# H723_AD9280_AD9708.net
KiCad netlist of a schematic drawn in EasyEDA Pro
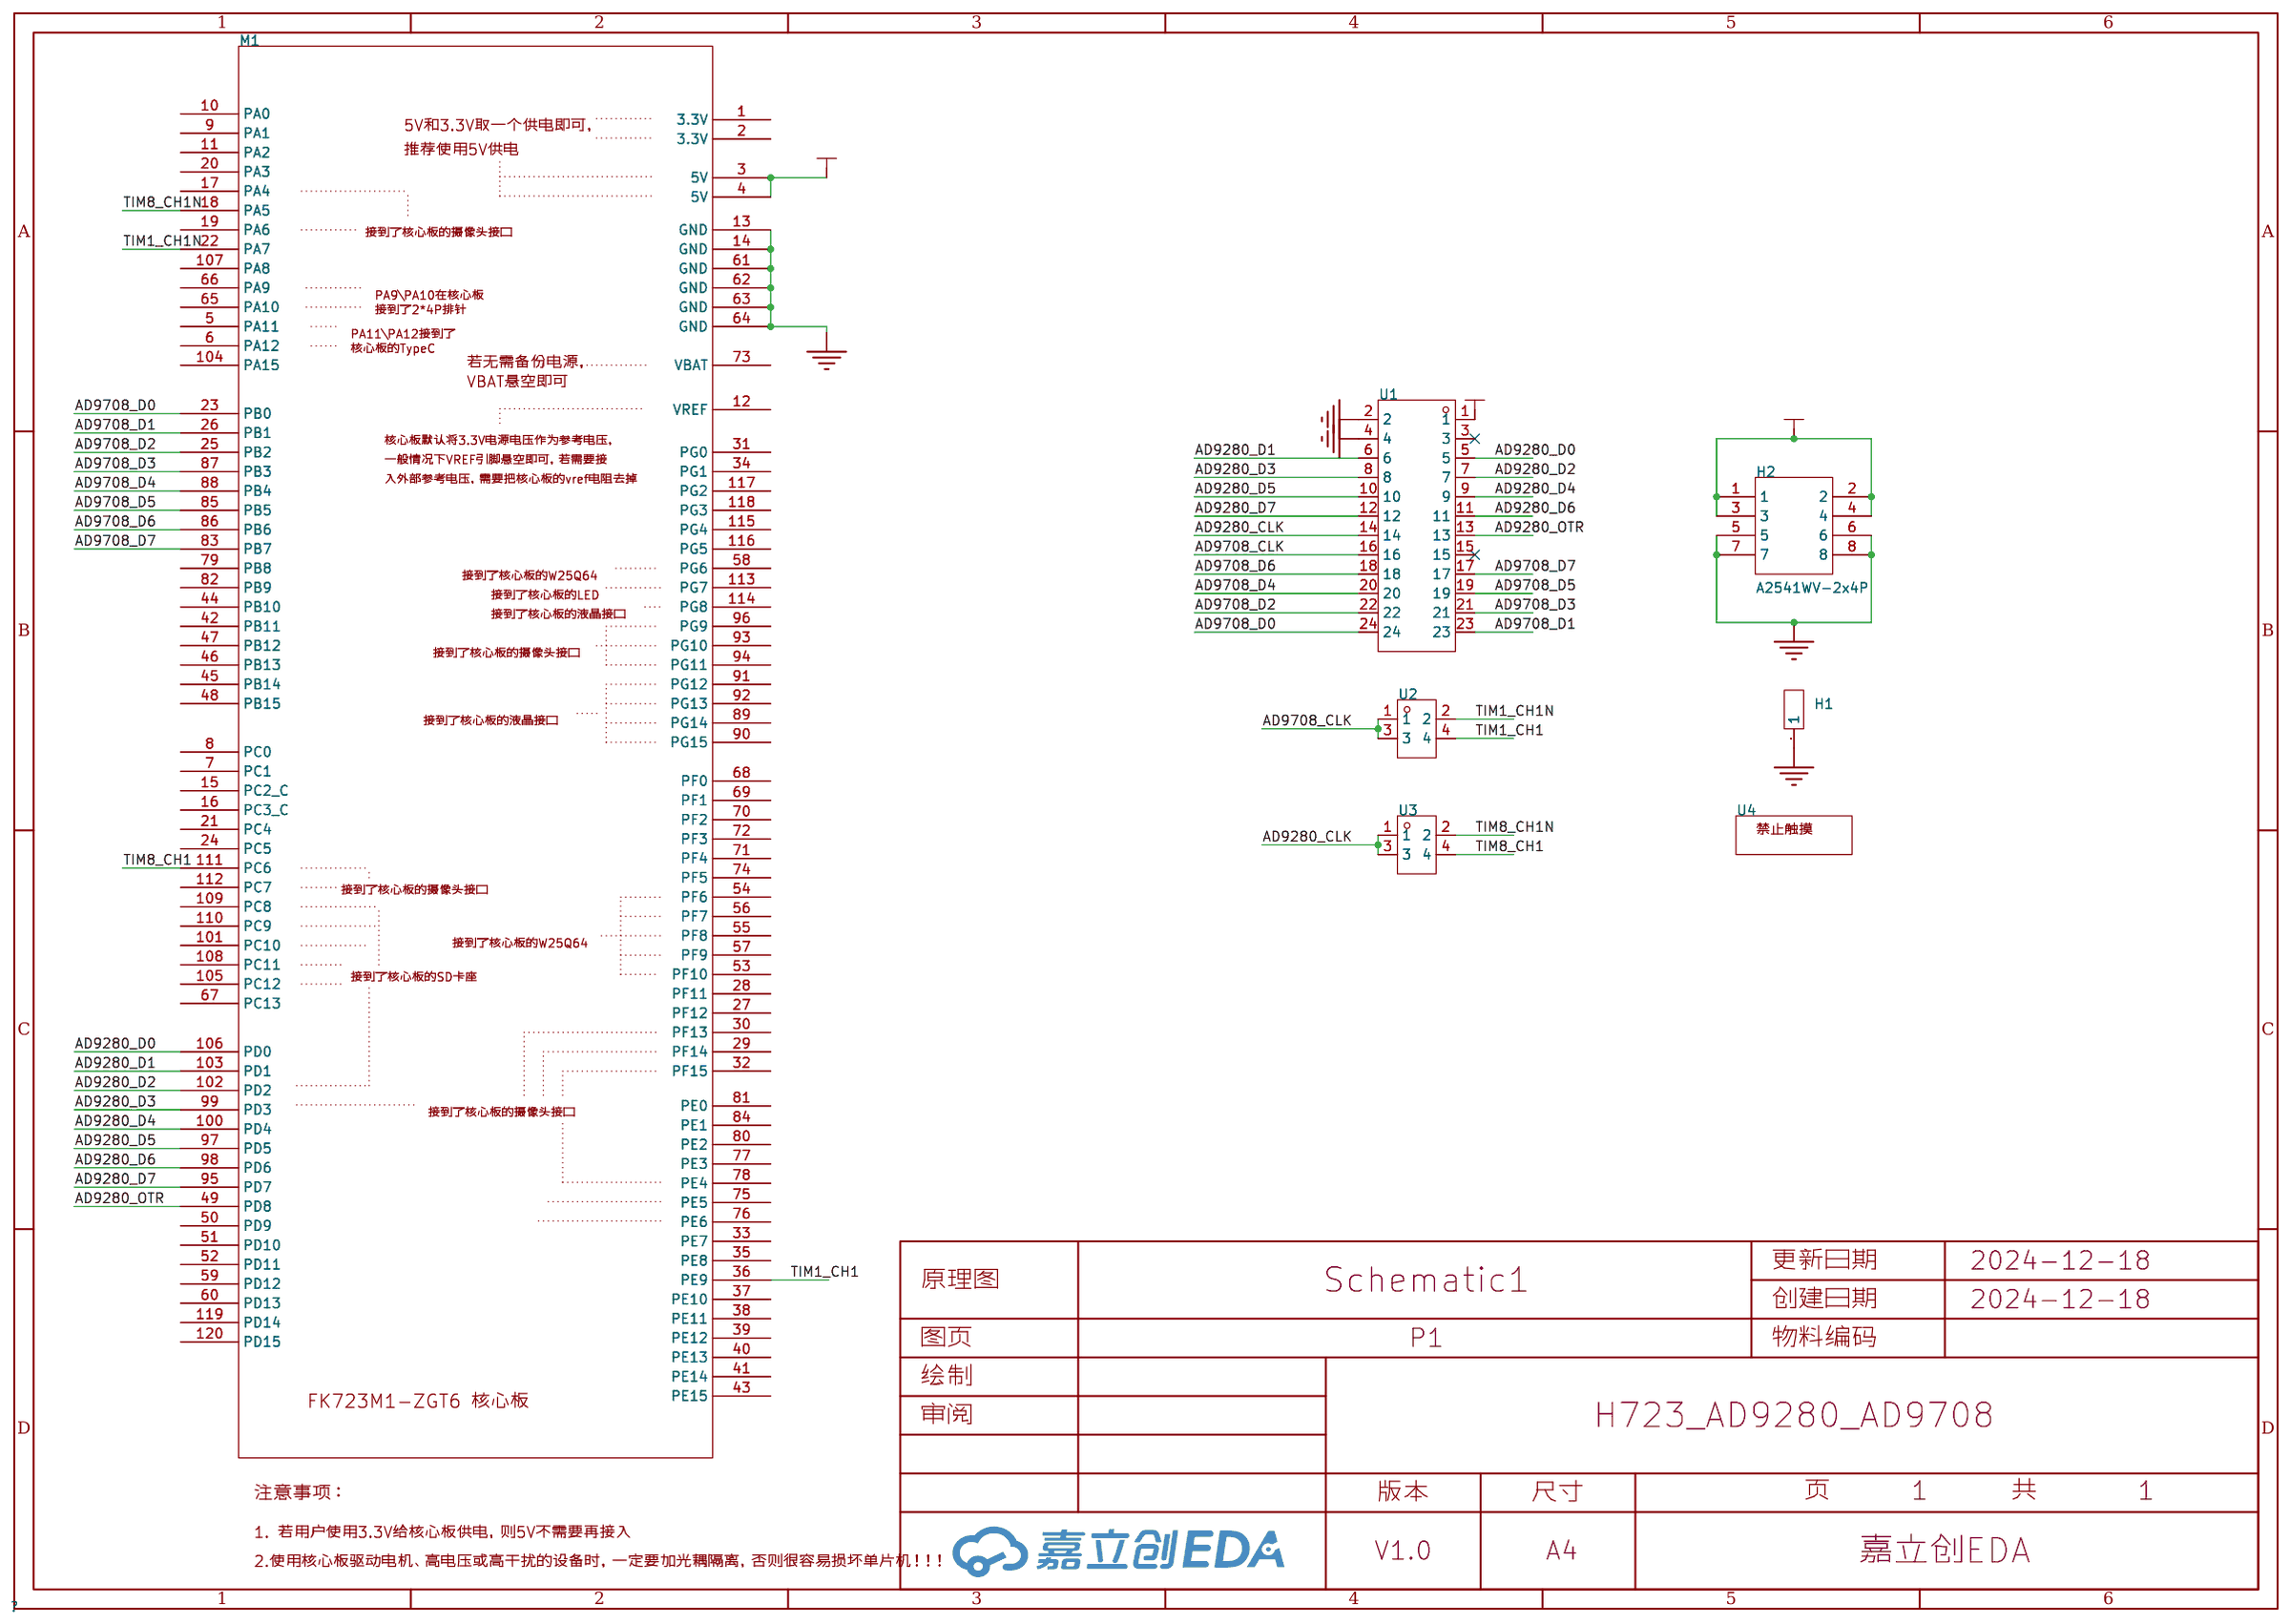
[diagram p0: schematic sheet]

(export (version "E")
  (design (tool "Eeschema 10.0.6"))
  (components
    (comp (ref "H1")
      (value "~")
      (footprint "easyedapro:HDR-TH_1P-V-M_XKB_X4611WV-01I-C28D40")
      (libsource (lib "easyedapro") (part "HDR_1x1"))
    )
    (comp (ref "H2")
      (value "A2541WV-2x4P")
      (footprint "easyedapro:HDR-TH_8P-P2.54-V-R2-C4-S2.54_A2541WV-2X4P")
      (fields (field (name "Manufacturer") "CJT(长江连接器)"))
      (libsource (lib "easyedapro") (part "A2541WV-2X4P"))
    )
    (comp (ref "M1")
      (value "~")
      (footprint "easyedapro:FK723M1-ZGT6")
      (libsource (lib "easyedapro") (part "FK723M1-ZGT6"))
    )
    (comp (ref "U1")
      (value "2541WV-2x12P")
      (footprint "easyedapro:HDR-TH_24P-P2.54-V-M-R2-C12-S2.54")
      (description "插针结构:2x12P;间距:2.54mm;安装类型:直插;排数:双排;总PIN位数:24P;配合针长度:6mm;塑高:2.54mm;端接针长度:3mm;")
      (fields (field (name "Manufacturer") "HanElectricity(瀚源)"))
      (libsource (lib "easyedapro") (part "2541WV-2X12P"))
    )
    (comp (ref "U2")
      (value "2541WV-2x02P")
      (footprint "easyedapro:HDR-TH_4P-P2.54-V-M-R2-C2-S2.54")
      (description "插针结构:2x2P;间距:2.54mm;安装类型:直插;排数:双排;总PIN位数:4P;配合针长度:6mm;塑高:2.54mm;端接针长度:3mm;")
      (fields (field (name "Manufacturer") "HanElectricity(瀚源)"))
      (libsource (lib "easyedapro") (part "2541WV-2X02P"))
    )
    (comp (ref "U3")
      (value "2541WV-2x02P")
      (footprint "easyedapro:HDR-TH_4P-P2.54-V-M-R2-C2-S2.54")
      (description "插针结构:2x2P;间距:2.54mm;安装类型:直插;排数:双排;总PIN位数:4P;配合针长度:6mm;塑高:2.54mm;端接针长度:3mm;")
      (fields (field (name "Manufacturer") "HanElectricity(瀚源)"))
      (libsource (lib "easyedapro") (part "2541WV-2X02P"))
    )
    (comp (ref "U4")
      (value "~")
      (footprint "easyedapro:禁止触摸LOGO")
      (libsource (lib "easyedapro") (part "禁止触摸LOGO"))
    )
  )
  (nets
    (net (code "1") (name "/AD9280_CLK") (class "Default")
      (node (ref "U1") (pin "14") (pinfunction "14_14") (pintype "unspecified"))
      (node (ref "U3") (pin "1") (pinfunction "1_1") (pintype "unspecified"))
      (node (ref "U3") (pin "3") (pinfunction "3_3") (pintype "unspecified"))
    )
    (net (code "2") (name "/AD9280_D0") (class "Default")
      (node (ref "M1") (pin "106") (pinfunction "PD0_106") (pintype "unspecified"))
      (node (ref "U1") (pin "5") (pinfunction "5_5") (pintype "unspecified"))
    )
    (net (code "3") (name "/AD9280_D1") (class "Default")
      (node (ref "M1") (pin "103") (pinfunction "PD1_103") (pintype "unspecified"))
      (node (ref "U1") (pin "6") (pinfunction "6_6") (pintype "unspecified"))
    )
    (net (code "4") (name "/AD9280_D2") (class "Default")
      (node (ref "M1") (pin "102") (pinfunction "PD2_102") (pintype "unspecified"))
      (node (ref "U1") (pin "7") (pinfunction "7_7") (pintype "unspecified"))
    )
    (net (code "5") (name "/AD9280_D3") (class "Default")
      (node (ref "M1") (pin "99") (pinfunction "PD3_99") (pintype "unspecified"))
      (node (ref "U1") (pin "8") (pinfunction "8_8") (pintype "unspecified"))
    )
    (net (code "6") (name "/AD9280_D4") (class "Default")
      (node (ref "M1") (pin "100") (pinfunction "PD4_100") (pintype "unspecified"))
      (node (ref "U1") (pin "9") (pinfunction "9_9") (pintype "unspecified"))
    )
    (net (code "7") (name "/AD9280_D5") (class "Default")
      (node (ref "M1") (pin "97") (pinfunction "PD5_97") (pintype "unspecified"))
      (node (ref "U1") (pin "10") (pinfunction "10_10") (pintype "unspecified"))
    )
    (net (code "8") (name "/AD9280_D6") (class "Default")
      (node (ref "M1") (pin "98") (pinfunction "PD6_98") (pintype "unspecified"))
      (node (ref "U1") (pin "11") (pinfunction "11_11") (pintype "unspecified"))
    )
    (net (code "9") (name "/AD9280_D7") (class "Default")
      (node (ref "M1") (pin "95") (pinfunction "PD7_95") (pintype "unspecified"))
      (node (ref "U1") (pin "12") (pinfunction "12_12") (pintype "unspecified"))
    )
    (net (code "10") (name "/AD9280_OTR") (class "Default")
      (node (ref "M1") (pin "49") (pinfunction "PD8_49") (pintype "unspecified"))
      (node (ref "U1") (pin "13") (pinfunction "13_13") (pintype "unspecified"))
    )
    (net (code "11") (name "/AD9708_CLK") (class "Default")
      (node (ref "U1") (pin "16") (pinfunction "16_16") (pintype "unspecified"))
      (node (ref "U2") (pin "1") (pinfunction "1_1") (pintype "unspecified"))
      (node (ref "U2") (pin "3") (pinfunction "3_3") (pintype "unspecified"))
    )
    (net (code "12") (name "/AD9708_D0") (class "Default")
      (node (ref "M1") (pin "23") (pinfunction "PB0_23") (pintype "unspecified"))
      (node (ref "U1") (pin "24") (pinfunction "24_24") (pintype "unspecified"))
    )
    (net (code "13") (name "/AD9708_D1") (class "Default")
      (node (ref "M1") (pin "26") (pinfunction "PB1_26") (pintype "unspecified"))
      (node (ref "U1") (pin "23") (pinfunction "23_23") (pintype "unspecified"))
    )
    (net (code "14") (name "/AD9708_D2") (class "Default")
      (node (ref "M1") (pin "25") (pinfunction "PB2_25") (pintype "unspecified"))
      (node (ref "U1") (pin "22") (pinfunction "22_22") (pintype "unspecified"))
    )
    (net (code "15") (name "/AD9708_D3") (class "Default")
      (node (ref "M1") (pin "87") (pinfunction "PB3_87") (pintype "unspecified"))
      (node (ref "U1") (pin "21") (pinfunction "21_21") (pintype "unspecified"))
    )
    (net (code "16") (name "/AD9708_D4") (class "Default")
      (node (ref "M1") (pin "88") (pinfunction "PB4_88") (pintype "unspecified"))
      (node (ref "U1") (pin "20") (pinfunction "20_20") (pintype "unspecified"))
    )
    (net (code "17") (name "/AD9708_D5") (class "Default")
      (node (ref "M1") (pin "85") (pinfunction "PB5_85") (pintype "unspecified"))
      (node (ref "U1") (pin "19") (pinfunction "19_19") (pintype "unspecified"))
    )
    (net (code "18") (name "/AD9708_D6") (class "Default")
      (node (ref "M1") (pin "86") (pinfunction "PB6_86") (pintype "unspecified"))
      (node (ref "U1") (pin "18") (pinfunction "18_18") (pintype "unspecified"))
    )
    (net (code "19") (name "/AD9708_D7") (class "Default")
      (node (ref "M1") (pin "83") (pinfunction "PB7_83") (pintype "unspecified"))
      (node (ref "U1") (pin "17") (pinfunction "17_17") (pintype "unspecified"))
    )
    (net (code "20") (name "/TIM1_CH1") (class "Default")
      (node (ref "M1") (pin "36") (pinfunction "PE9_36") (pintype "unspecified"))
      (node (ref "U2") (pin "4") (pinfunction "4_4") (pintype "unspecified"))
    )
    (net (code "21") (name "/TIM1_CH1N") (class "Default")
      (node (ref "M1") (pin "22") (pinfunction "PA7_22") (pintype "unspecified"))
      (node (ref "U2") (pin "2") (pinfunction "2_2") (pintype "unspecified"))
    )
    (net (code "22") (name "/TIM8_CH1") (class "Default")
      (node (ref "M1") (pin "111") (pinfunction "PC6_111") (pintype "unspecified"))
      (node (ref "U3") (pin "4") (pinfunction "4_4") (pintype "unspecified"))
    )
    (net (code "23") (name "/TIM8_CH1N") (class "Default")
      (node (ref "M1") (pin "18") (pinfunction "PA5_18") (pintype "unspecified"))
      (node (ref "U3") (pin "2") (pinfunction "2_2") (pintype "unspecified"))
    )
    (net (code "24") (name "5V") (class "Default")
      (node (ref "H2") (pin "1") (pinfunction "1_1") (pintype "unspecified"))
      (node (ref "H2") (pin "2") (pinfunction "2_2") (pintype "unspecified"))
      (node (ref "H2") (pin "3") (pinfunction "3_3") (pintype "unspecified"))
      (node (ref "H2") (pin "4") (pinfunction "4_4") (pintype "unspecified"))
      (node (ref "M1") (pin "3") (pinfunction "5V_3") (pintype "unspecified"))
      (node (ref "M1") (pin "4") (pinfunction "5V_4") (pintype "unspecified"))
      (node (ref "U1") (pin "1") (pinfunction "1_1") (pintype "unspecified"))
    )
    (net (code "25") (name "GND") (class "Default")
      (node (ref "H1") (pin "1") (pinfunction "1_1") (pintype "unspecified"))
      (node (ref "H2") (pin "5") (pinfunction "5_5") (pintype "unspecified"))
      (node (ref "H2") (pin "6") (pinfunction "6_6") (pintype "unspecified"))
      (node (ref "H2") (pin "7") (pinfunction "7_7") (pintype "unspecified"))
      (node (ref "H2") (pin "8") (pinfunction "8_8") (pintype "unspecified"))
      (node (ref "M1") (pin "13") (pinfunction "GND_13") (pintype "unspecified"))
      (node (ref "M1") (pin "14") (pinfunction "GND_14") (pintype "unspecified"))
      (node (ref "M1") (pin "61") (pinfunction "GND_61") (pintype "unspecified"))
      (node (ref "M1") (pin "62") (pinfunction "GND_62") (pintype "unspecified"))
      (node (ref "M1") (pin "63") (pinfunction "GND_63") (pintype "unspecified"))
      (node (ref "M1") (pin "64") (pinfunction "GND_64") (pintype "unspecified"))
      (node (ref "U1") (pin "2") (pinfunction "2_2") (pintype "unspecified"))
      (node (ref "U1") (pin "4") (pinfunction "4_4") (pintype "unspecified"))
    )
    (net (code "26") (name "unconnected-(M1-3.3V-Pad1)") (class "Default")
      (node (ref "M1") (pin "1") (pinfunction "3.3V_1") (pintype "unspecified"))
    )
    (net (code "27") (name "unconnected-(M1-3.3V-Pad2)") (class "Default")
      (node (ref "M1") (pin "2") (pinfunction "3.3V_2") (pintype "unspecified"))
    )
    (net (code "28") (name "unconnected-(M1-PA0-Pad10)") (class "Default")
      (node (ref "M1") (pin "10") (pinfunction "PA0_10") (pintype "unspecified"))
    )
    (net (code "29") (name "unconnected-(M1-PA1-Pad9)") (class "Default")
      (node (ref "M1") (pin "9") (pinfunction "PA1_9") (pintype "unspecified"))
    )
    (net (code "30") (name "unconnected-(M1-PA2-Pad11)") (class "Default")
      (node (ref "M1") (pin "11") (pinfunction "PA2_11") (pintype "unspecified"))
    )
    (net (code "31") (name "unconnected-(M1-PA3-Pad20)") (class "Default")
      (node (ref "M1") (pin "20") (pinfunction "PA3_20") (pintype "unspecified"))
    )
    (net (code "32") (name "unconnected-(M1-PA4-Pad17)") (class "Default")
      (node (ref "M1") (pin "17") (pinfunction "PA4_17") (pintype "unspecified"))
    )
    (net (code "33") (name "unconnected-(M1-PA6-Pad19)") (class "Default")
      (node (ref "M1") (pin "19") (pinfunction "PA6_19") (pintype "unspecified"))
    )
    (net (code "34") (name "unconnected-(M1-PA8-Pad107)") (class "Default")
      (node (ref "M1") (pin "107") (pinfunction "PA8_107") (pintype "unspecified"))
    )
    (net (code "35") (name "unconnected-(M1-PA9-Pad66)") (class "Default")
      (node (ref "M1") (pin "66") (pinfunction "PA9_66") (pintype "unspecified"))
    )
    (net (code "36") (name "unconnected-(M1-PA10-Pad65)") (class "Default")
      (node (ref "M1") (pin "65") (pinfunction "PA10_65") (pintype "unspecified"))
    )
    (net (code "37") (name "unconnected-(M1-PA11-Pad5)") (class "Default")
      (node (ref "M1") (pin "5") (pinfunction "PA11_5") (pintype "unspecified"))
    )
    (net (code "38") (name "unconnected-(M1-PA12-Pad6)") (class "Default")
      (node (ref "M1") (pin "6") (pinfunction "PA12_6") (pintype "unspecified"))
    )
    (net (code "39") (name "unconnected-(M1-PA15-Pad104)") (class "Default")
      (node (ref "M1") (pin "104") (pinfunction "PA15_104") (pintype "unspecified"))
    )
    (net (code "40") (name "unconnected-(M1-PB8-Pad79)") (class "Default")
      (node (ref "M1") (pin "79") (pinfunction "PB8_79") (pintype "unspecified"))
    )
    (net (code "41") (name "unconnected-(M1-PB9-Pad82)") (class "Default")
      (node (ref "M1") (pin "82") (pinfunction "PB9_82") (pintype "unspecified"))
    )
    (net (code "42") (name "unconnected-(M1-PB10-Pad44)") (class "Default")
      (node (ref "M1") (pin "44") (pinfunction "PB10_44") (pintype "unspecified"))
    )
    (net (code "43") (name "unconnected-(M1-PB11-Pad42)") (class "Default")
      (node (ref "M1") (pin "42") (pinfunction "PB11_42") (pintype "unspecified"))
    )
    (net (code "44") (name "unconnected-(M1-PB12-Pad47)") (class "Default")
      (node (ref "M1") (pin "47") (pinfunction "PB12_47") (pintype "unspecified"))
    )
    (net (code "45") (name "unconnected-(M1-PB13-Pad46)") (class "Default")
      (node (ref "M1") (pin "46") (pinfunction "PB13_46") (pintype "unspecified"))
    )
    (net (code "46") (name "unconnected-(M1-PB14-Pad45)") (class "Default")
      (node (ref "M1") (pin "45") (pinfunction "PB14_45") (pintype "unspecified"))
    )
    (net (code "47") (name "unconnected-(M1-PB15-Pad48)") (class "Default")
      (node (ref "M1") (pin "48") (pinfunction "PB15_48") (pintype "unspecified"))
    )
    (net (code "48") (name "unconnected-(M1-PC0-Pad8)") (class "Default")
      (node (ref "M1") (pin "8") (pinfunction "PC0_8") (pintype "unspecified"))
    )
    (net (code "49") (name "unconnected-(M1-PC1-Pad7)") (class "Default")
      (node (ref "M1") (pin "7") (pinfunction "PC1_7") (pintype "unspecified"))
    )
    (net (code "50") (name "unconnected-(M1-PC2_C-Pad15)") (class "Default")
      (node (ref "M1") (pin "15") (pinfunction "PC2_C_15") (pintype "unspecified"))
    )
    (net (code "51") (name "unconnected-(M1-PC3_C-Pad16)") (class "Default")
      (node (ref "M1") (pin "16") (pinfunction "PC3_C_16") (pintype "unspecified"))
    )
    (net (code "52") (name "unconnected-(M1-PC4-Pad21)") (class "Default")
      (node (ref "M1") (pin "21") (pinfunction "PC4_21") (pintype "unspecified"))
    )
    (net (code "53") (name "unconnected-(M1-PC5-Pad24)") (class "Default")
      (node (ref "M1") (pin "24") (pinfunction "PC5_24") (pintype "unspecified"))
    )
    (net (code "54") (name "unconnected-(M1-PC7-Pad112)") (class "Default")
      (node (ref "M1") (pin "112") (pinfunction "PC7_112") (pintype "unspecified"))
    )
    (net (code "55") (name "unconnected-(M1-PC8-Pad109)") (class "Default")
      (node (ref "M1") (pin "109") (pinfunction "PC8_109") (pintype "unspecified"))
    )
    (net (code "56") (name "unconnected-(M1-PC9-Pad110)") (class "Default")
      (node (ref "M1") (pin "110") (pinfunction "PC9_110") (pintype "unspecified"))
    )
    (net (code "57") (name "unconnected-(M1-PC10-Pad101)") (class "Default")
      (node (ref "M1") (pin "101") (pinfunction "PC10_101") (pintype "unspecified"))
    )
    (net (code "58") (name "unconnected-(M1-PC11-Pad108)") (class "Default")
      (node (ref "M1") (pin "108") (pinfunction "PC11_108") (pintype "unspecified"))
    )
    (net (code "59") (name "unconnected-(M1-PC12-Pad105)") (class "Default")
      (node (ref "M1") (pin "105") (pinfunction "PC12_105") (pintype "unspecified"))
    )
    (net (code "60") (name "unconnected-(M1-PC13-Pad67)") (class "Default")
      (node (ref "M1") (pin "67") (pinfunction "PC13_67") (pintype "unspecified"))
    )
    (net (code "61") (name "unconnected-(M1-PD9-Pad50)") (class "Default")
      (node (ref "M1") (pin "50") (pinfunction "PD9_50") (pintype "unspecified"))
    )
    (net (code "62") (name "unconnected-(M1-PD10-Pad51)") (class "Default")
      (node (ref "M1") (pin "51") (pinfunction "PD10_51") (pintype "unspecified"))
    )
    (net (code "63") (name "unconnected-(M1-PD11-Pad52)") (class "Default")
      (node (ref "M1") (pin "52") (pinfunction "PD11_52") (pintype "unspecified"))
    )
    (net (code "64") (name "unconnected-(M1-PD12-Pad59)") (class "Default")
      (node (ref "M1") (pin "59") (pinfunction "PD12_59") (pintype "unspecified"))
    )
    (net (code "65") (name "unconnected-(M1-PD13-Pad60)") (class "Default")
      (node (ref "M1") (pin "60") (pinfunction "PD13_60") (pintype "unspecified"))
    )
    (net (code "66") (name "unconnected-(M1-PD14-Pad119)") (class "Default")
      (node (ref "M1") (pin "119") (pinfunction "PD14_119") (pintype "unspecified"))
    )
    (net (code "67") (name "unconnected-(M1-PD15-Pad120)") (class "Default")
      (node (ref "M1") (pin "120") (pinfunction "PD15_120") (pintype "unspecified"))
    )
    (net (code "68") (name "unconnected-(M1-PE0-Pad81)") (class "Default")
      (node (ref "M1") (pin "81") (pinfunction "PE0_81") (pintype "unspecified"))
    )
    (net (code "69") (name "unconnected-(M1-PE1-Pad84)") (class "Default")
      (node (ref "M1") (pin "84") (pinfunction "PE1_84") (pintype "unspecified"))
    )
    (net (code "70") (name "unconnected-(M1-PE2-Pad80)") (class "Default")
      (node (ref "M1") (pin "80") (pinfunction "PE2_80") (pintype "unspecified"))
    )
    (net (code "71") (name "unconnected-(M1-PE3-Pad77)") (class "Default")
      (node (ref "M1") (pin "77") (pinfunction "PE3_77") (pintype "unspecified"))
    )
    (net (code "72") (name "unconnected-(M1-PE4-Pad78)") (class "Default")
      (node (ref "M1") (pin "78") (pinfunction "PE4_78") (pintype "unspecified"))
    )
    (net (code "73") (name "unconnected-(M1-PE5-Pad75)") (class "Default")
      (node (ref "M1") (pin "75") (pinfunction "PE5_75") (pintype "unspecified"))
    )
    (net (code "74") (name "unconnected-(M1-PE6-Pad76)") (class "Default")
      (node (ref "M1") (pin "76") (pinfunction "PE6_76") (pintype "unspecified"))
    )
    (net (code "75") (name "unconnected-(M1-PE7-Pad33)") (class "Default")
      (node (ref "M1") (pin "33") (pinfunction "PE7_33") (pintype "unspecified"))
    )
    (net (code "76") (name "unconnected-(M1-PE8-Pad35)") (class "Default")
      (node (ref "M1") (pin "35") (pinfunction "PE8_35") (pintype "unspecified"))
    )
    (net (code "77") (name "unconnected-(M1-PE10-Pad37)") (class "Default")
      (node (ref "M1") (pin "37") (pinfunction "PE10_37") (pintype "unspecified"))
    )
    (net (code "78") (name "unconnected-(M1-PE11-Pad38)") (class "Default")
      (node (ref "M1") (pin "38") (pinfunction "PE11_38") (pintype "unspecified"))
    )
    (net (code "79") (name "unconnected-(M1-PE12-Pad39)") (class "Default")
      (node (ref "M1") (pin "39") (pinfunction "PE12_39") (pintype "unspecified"))
    )
    (net (code "80") (name "unconnected-(M1-PE13-Pad40)") (class "Default")
      (node (ref "M1") (pin "40") (pinfunction "PE13_40") (pintype "unspecified"))
    )
    (net (code "81") (name "unconnected-(M1-PE14-Pad41)") (class "Default")
      (node (ref "M1") (pin "41") (pinfunction "PE14_41") (pintype "unspecified"))
    )
    (net (code "82") (name "unconnected-(M1-PE15-Pad43)") (class "Default")
      (node (ref "M1") (pin "43") (pinfunction "PE15_43") (pintype "unspecified"))
    )
    (net (code "83") (name "unconnected-(M1-PF0-Pad68)") (class "Default")
      (node (ref "M1") (pin "68") (pinfunction "PF0_68") (pintype "unspecified"))
    )
    (net (code "84") (name "unconnected-(M1-PF1-Pad69)") (class "Default")
      (node (ref "M1") (pin "69") (pinfunction "PF1_69") (pintype "unspecified"))
    )
    (net (code "85") (name "unconnected-(M1-PF2-Pad70)") (class "Default")
      (node (ref "M1") (pin "70") (pinfunction "PF2_70") (pintype "unspecified"))
    )
    (net (code "86") (name "unconnected-(M1-PF3-Pad72)") (class "Default")
      (node (ref "M1") (pin "72") (pinfunction "PF3_72") (pintype "unspecified"))
    )
    (net (code "87") (name "unconnected-(M1-PF4-Pad71)") (class "Default")
      (node (ref "M1") (pin "71") (pinfunction "PF4_71") (pintype "unspecified"))
    )
    (net (code "88") (name "unconnected-(M1-PF5-Pad74)") (class "Default")
      (node (ref "M1") (pin "74") (pinfunction "PF5_74") (pintype "unspecified"))
    )
    (net (code "89") (name "unconnected-(M1-PF6-Pad54)") (class "Default")
      (node (ref "M1") (pin "54") (pinfunction "PF6_54") (pintype "unspecified"))
    )
    (net (code "90") (name "unconnected-(M1-PF7-Pad56)") (class "Default")
      (node (ref "M1") (pin "56") (pinfunction "PF7_56") (pintype "unspecified"))
    )
    (net (code "91") (name "unconnected-(M1-PF8-Pad55)") (class "Default")
      (node (ref "M1") (pin "55") (pinfunction "PF8_55") (pintype "unspecified"))
    )
    (net (code "92") (name "unconnected-(M1-PF9-Pad57)") (class "Default")
      (node (ref "M1") (pin "57") (pinfunction "PF9_57") (pintype "unspecified"))
    )
    (net (code "93") (name "unconnected-(M1-PF10-Pad53)") (class "Default")
      (node (ref "M1") (pin "53") (pinfunction "PF10_53") (pintype "unspecified"))
    )
    (net (code "94") (name "unconnected-(M1-PF11-Pad28)") (class "Default")
      (node (ref "M1") (pin "28") (pinfunction "PF11_28") (pintype "unspecified"))
    )
    (net (code "95") (name "unconnected-(M1-PF12-Pad27)") (class "Default")
      (node (ref "M1") (pin "27") (pinfunction "PF12_27") (pintype "unspecified"))
    )
    (net (code "96") (name "unconnected-(M1-PF13-Pad30)") (class "Default")
      (node (ref "M1") (pin "30") (pinfunction "PF13_30") (pintype "unspecified"))
    )
    (net (code "97") (name "unconnected-(M1-PF14-Pad29)") (class "Default")
      (node (ref "M1") (pin "29") (pinfunction "PF14_29") (pintype "unspecified"))
    )
    (net (code "98") (name "unconnected-(M1-PF15-Pad32)") (class "Default")
      (node (ref "M1") (pin "32") (pinfunction "PF15_32") (pintype "unspecified"))
    )
    (net (code "99") (name "unconnected-(M1-PG0-Pad31)") (class "Default")
      (node (ref "M1") (pin "31") (pinfunction "PG0_31") (pintype "unspecified"))
    )
    (net (code "100") (name "unconnected-(M1-PG1-Pad34)") (class "Default")
      (node (ref "M1") (pin "34") (pinfunction "PG1_34") (pintype "unspecified"))
    )
    (net (code "101") (name "unconnected-(M1-PG2-Pad117)") (class "Default")
      (node (ref "M1") (pin "117") (pinfunction "PG2_117") (pintype "unspecified"))
    )
    (net (code "102") (name "unconnected-(M1-PG3-Pad118)") (class "Default")
      (node (ref "M1") (pin "118") (pinfunction "PG3_118") (pintype "unspecified"))
    )
    (net (code "103") (name "unconnected-(M1-PG4-Pad115)") (class "Default")
      (node (ref "M1") (pin "115") (pinfunction "PG4_115") (pintype "unspecified"))
    )
    (net (code "104") (name "unconnected-(M1-PG5-Pad116)") (class "Default")
      (node (ref "M1") (pin "116") (pinfunction "PG5_116") (pintype "unspecified"))
    )
    (net (code "105") (name "unconnected-(M1-PG6-Pad58)") (class "Default")
      (node (ref "M1") (pin "58") (pinfunction "PG6_58") (pintype "unspecified"))
    )
    (net (code "106") (name "unconnected-(M1-PG7-Pad113)") (class "Default")
      (node (ref "M1") (pin "113") (pinfunction "PG7_113") (pintype "unspecified"))
    )
    (net (code "107") (name "unconnected-(M1-PG8-Pad114)") (class "Default")
      (node (ref "M1") (pin "114") (pinfunction "PG8_114") (pintype "unspecified"))
    )
    (net (code "108") (name "unconnected-(M1-PG9-Pad96)") (class "Default")
      (node (ref "M1") (pin "96") (pinfunction "PG9_96") (pintype "unspecified"))
    )
    (net (code "109") (name "unconnected-(M1-PG10-Pad93)") (class "Default")
      (node (ref "M1") (pin "93") (pinfunction "PG10_93") (pintype "unspecified"))
    )
    (net (code "110") (name "unconnected-(M1-PG11-Pad94)") (class "Default")
      (node (ref "M1") (pin "94") (pinfunction "PG11_94") (pintype "unspecified"))
    )
    (net (code "111") (name "unconnected-(M1-PG12-Pad91)") (class "Default")
      (node (ref "M1") (pin "91") (pinfunction "PG12_91") (pintype "unspecified"))
    )
    (net (code "112") (name "unconnected-(M1-PG13-Pad92)") (class "Default")
      (node (ref "M1") (pin "92") (pinfunction "PG13_92") (pintype "unspecified"))
    )
    (net (code "113") (name "unconnected-(M1-PG14-Pad89)") (class "Default")
      (node (ref "M1") (pin "89") (pinfunction "PG14_89") (pintype "unspecified"))
    )
    (net (code "114") (name "unconnected-(M1-PG15-Pad90)") (class "Default")
      (node (ref "M1") (pin "90") (pinfunction "PG15_90") (pintype "unspecified"))
    )
    (net (code "115") (name "unconnected-(M1-VBAT-Pad73)") (class "Default")
      (node (ref "M1") (pin "73") (pinfunction "VBAT_73") (pintype "unspecified"))
    )
    (net (code "116") (name "unconnected-(M1-VREF-Pad12)") (class "Default")
      (node (ref "M1") (pin "12") (pinfunction "VREF_12") (pintype "unspecified"))
    )
    (net (code "117") (name "unconnected-(U1-Pad3)") (class "Default")
      (node (ref "U1") (pin "3") (pinfunction "3_3") (pintype "unspecified+no_connect"))
    )
    (net (code "118") (name "unconnected-(U1-Pad15)") (class "Default")
      (node (ref "U1") (pin "15") (pinfunction "15_15") (pintype "unspecified+no_connect"))
    )
  )
)
